# LabPower_test2.net
KiCad netlist of a schematic drawn in EAGLE
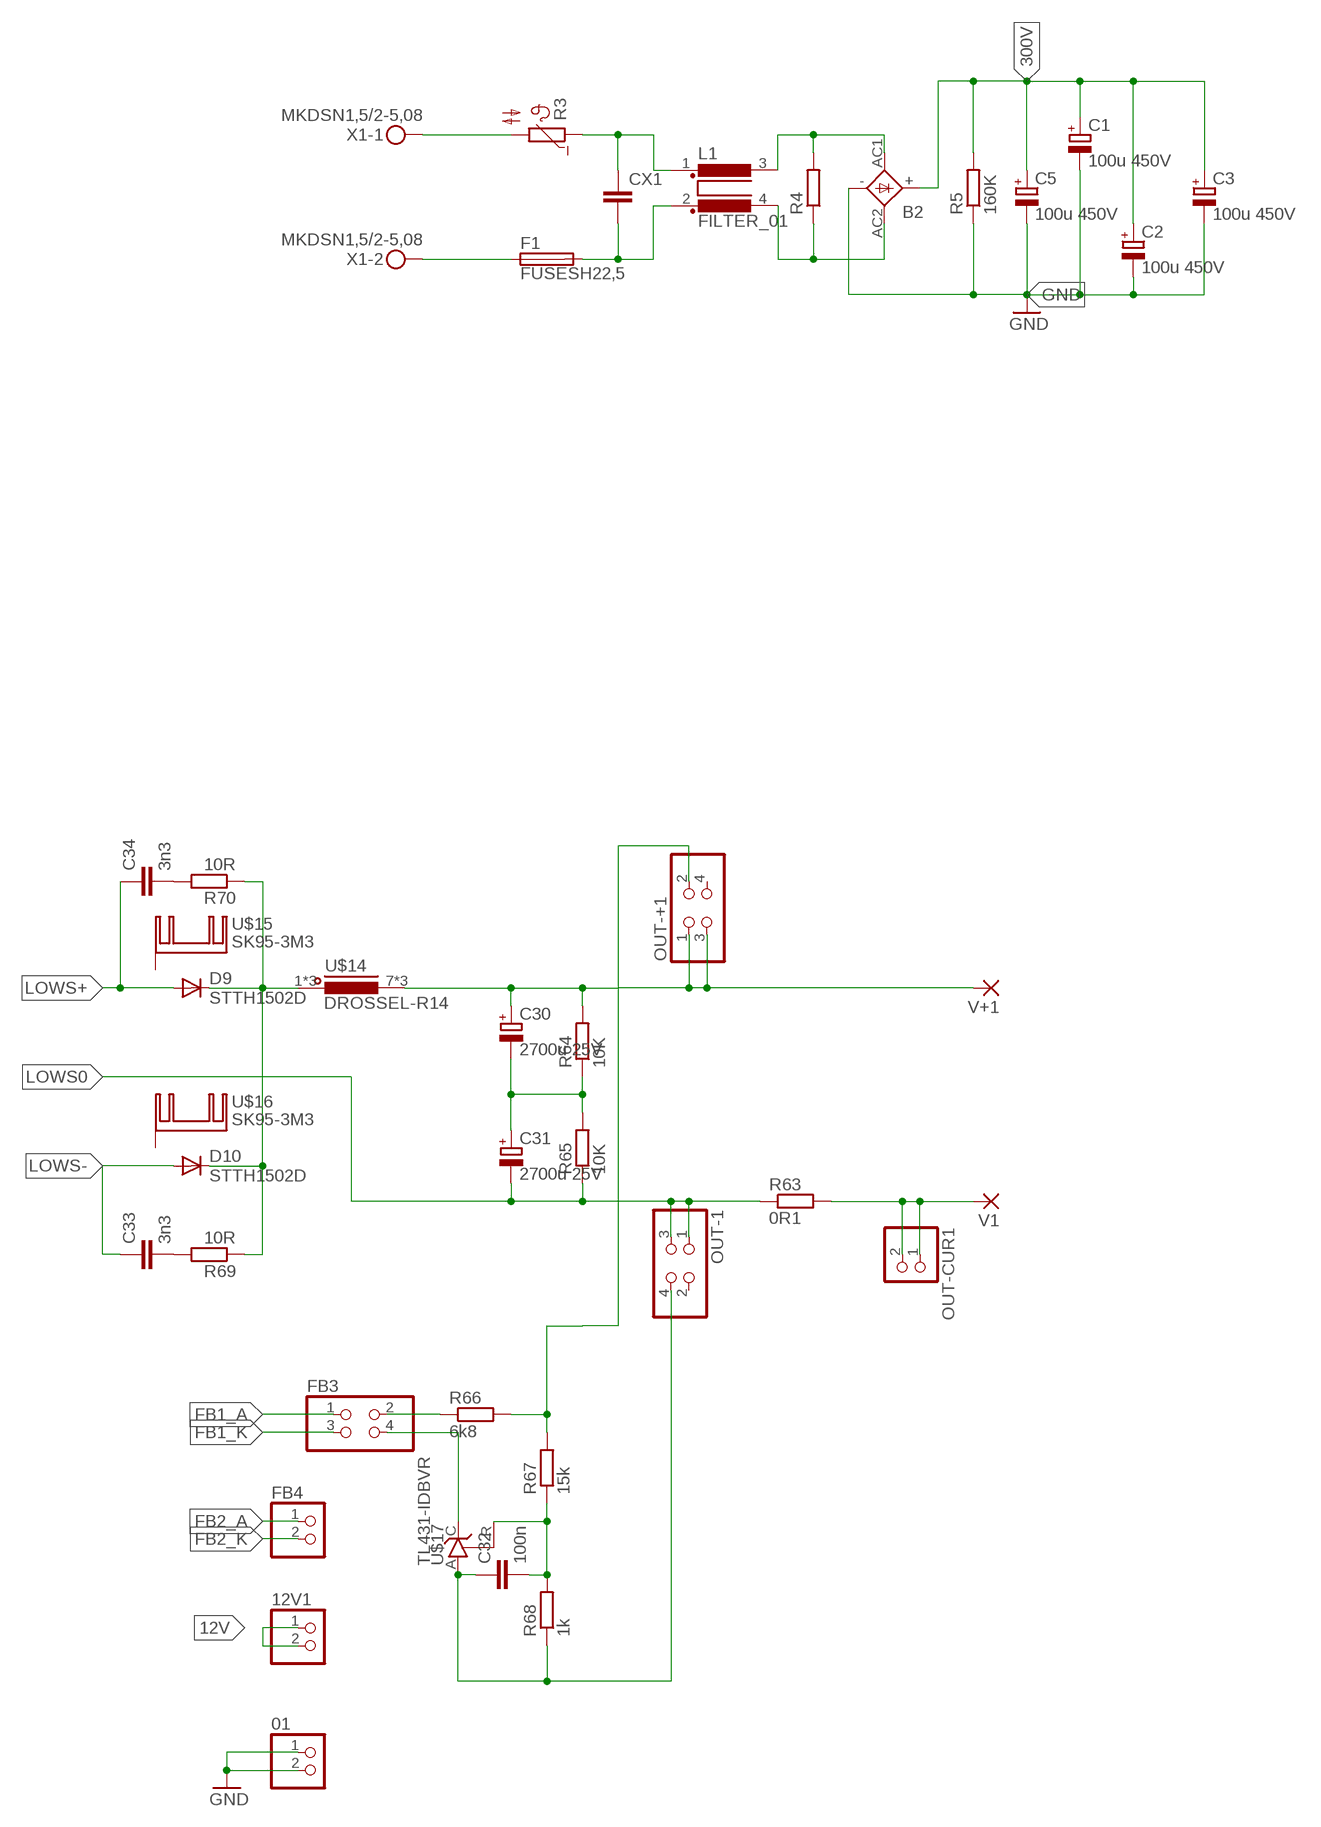
[diagram p0: schematic, sheet 1, part 1 of 2]
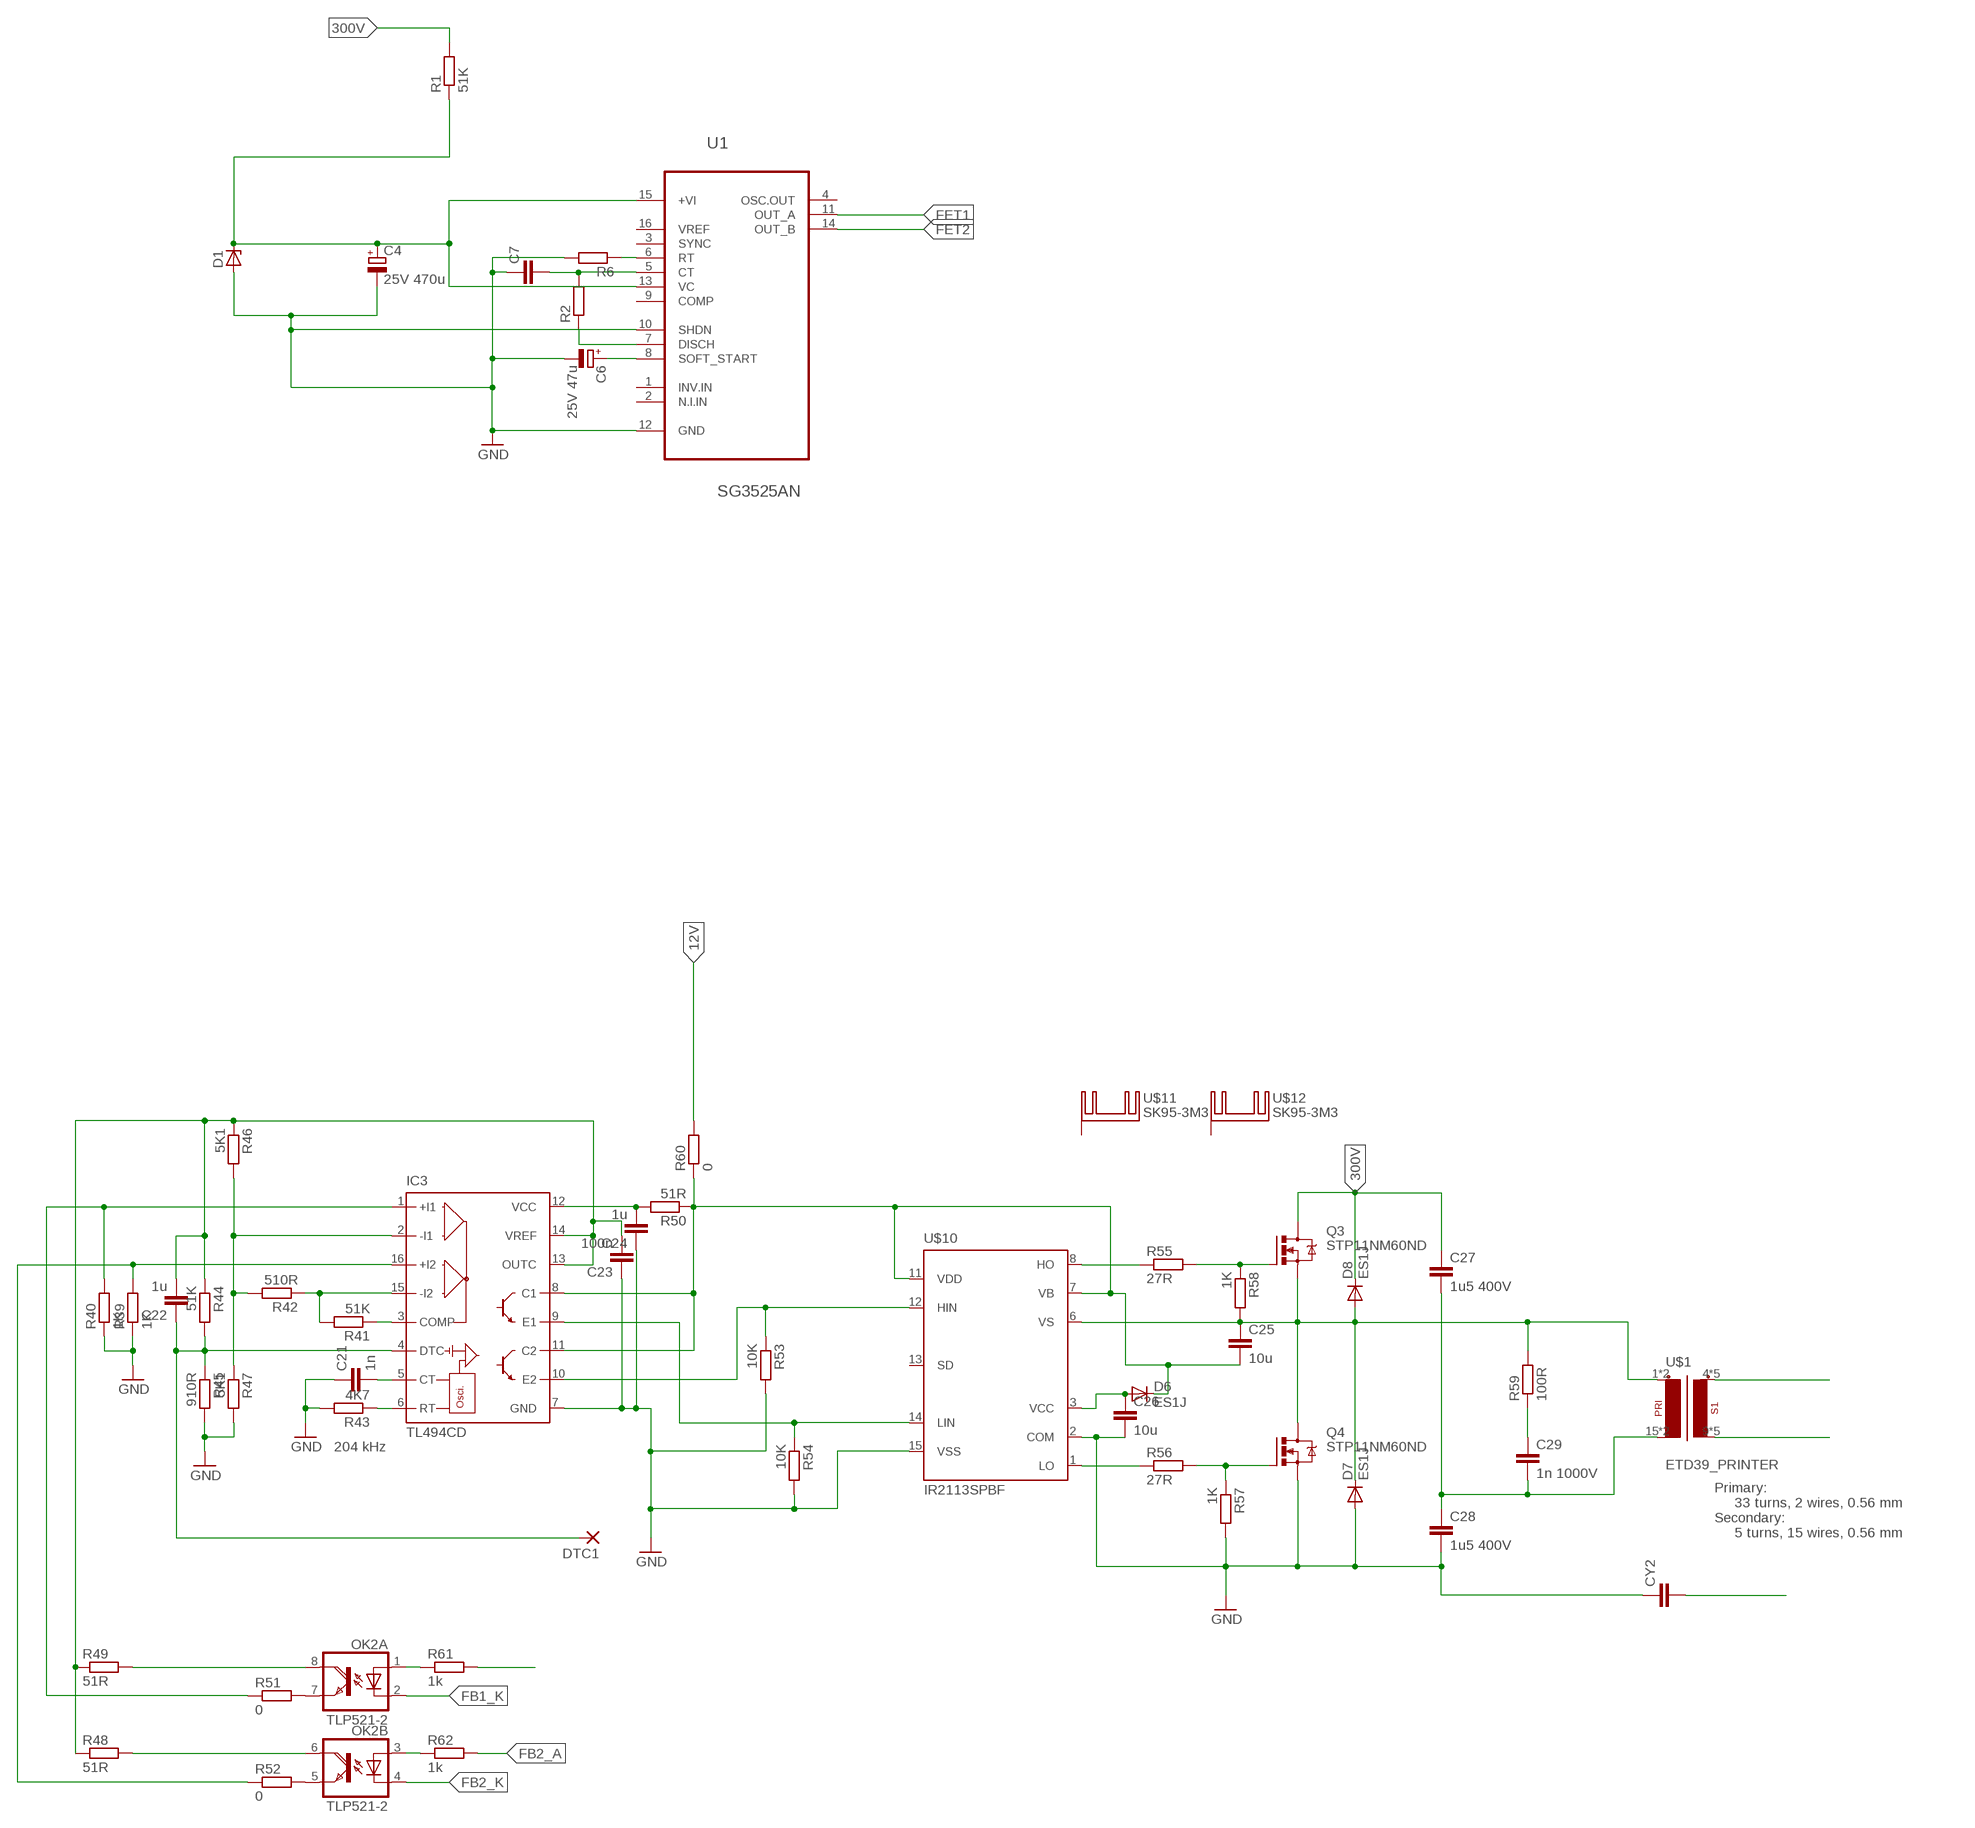
[diagram p1: schematic, sheet 1, part 2 of 2]

(export (version "E")
  (design (tool "Eeschema 10.0.6"))
  (components
    (comp (ref "01")
      (value "PINHD-1X2")
      (footprint "eagle-import:1X02")
      (libsource (lib "eagle-import") (part "PINHD-1X2"))
    )
    (comp (ref "12V1")
      (value "PINHD-1X2")
      (footprint "eagle-import:1X02")
      (libsource (lib "eagle-import") (part "PINHD-1X2"))
    )
    (comp (ref "B2")
      (value "KBL")
      (footprint "eagle-import:KBL")
      (libsource (lib "eagle-import") (part "KBL"))
    )
    (comp (ref "C1")
      (value "100u 450V")
      (footprint "eagle-import:EB22,5D")
      (libsource (lib "eagle-import") (part "CPOL-EUE10-22.5"))
    )
    (comp (ref "C2")
      (value "100u 450V")
      (footprint "eagle-import:EB22,5D")
      (libsource (lib "eagle-import") (part "CPOL-EUE10-22.5"))
    )
    (comp (ref "C3")
      (value "100u 450V")
      (footprint "eagle-import:EB22,5D")
      (libsource (lib "eagle-import") (part "CPOL-EUE10-22.5"))
    )
    (comp (ref "C4")
      (value "25V 470u")
      (footprint "eagle-import:E2,5-7")
      (libsource (lib "eagle-import") (part "CPOL-EUE2.5-7"))
    )
    (comp (ref "C5")
      (value "100u 450V")
      (footprint "eagle-import:EB22,5D")
      (libsource (lib "eagle-import") (part "CPOL-EUE10-22.5"))
    )
    (comp (ref "C6")
      (value "25V 47u")
      (footprint "eagle-import:E2,5-7")
      (libsource (lib "eagle-import") (part "CPOL-EUE2.5-7"))
    )
    (comp (ref "C7")
      (value "C-EUC0805")
      (footprint "eagle-import:C0805")
      (libsource (lib "eagle-import") (part "C-EUC0805"))
    )
    (comp (ref "C21")
      (value "1n")
      (footprint "eagle-import:C0805")
      (libsource (lib "eagle-import") (part "C-EUC0805"))
    )
    (comp (ref "C22")
      (value "1u")
      (footprint "eagle-import:C0805")
      (libsource (lib "eagle-import") (part "C-EUC0805"))
    )
    (comp (ref "C23")
      (value "100n")
      (footprint "eagle-import:C0805")
      (libsource (lib "eagle-import") (part "C-EUC0805"))
    )
    (comp (ref "C24")
      (value "1u")
      (footprint "eagle-import:C0805")
      (libsource (lib "eagle-import") (part "C-EUC0805"))
    )
    (comp (ref "C25")
      (value "10u")
      (footprint "eagle-import:C0805")
      (libsource (lib "eagle-import") (part "C-EUC0805"))
    )
    (comp (ref "C26")
      (value "10u")
      (footprint "eagle-import:C0805")
      (libsource (lib "eagle-import") (part "C-EUC0805"))
    )
    (comp (ref "C27")
      (value "1u5 400V")
      (footprint "eagle-import:C225-087X268")
      (libsource (lib "eagle-import") (part "C-EU225-087X268"))
    )
    (comp (ref "C28")
      (value "1u5 400V")
      (footprint "eagle-import:C225-087X268")
      (libsource (lib "eagle-import") (part "C-EU225-087X268"))
    )
    (comp (ref "C29")
      (value "1n 1000V")
      (footprint "eagle-import:C050-025X075")
      (libsource (lib "eagle-import") (part "C-EU050-025X075"))
    )
    (comp (ref "C30")
      (value "2700u 25V")
      (footprint "eagle-import:E7,5-18")
      (libsource (lib "eagle-import") (part "CPOL-EUE7.5-18"))
    )
    (comp (ref "C31")
      (value "2700u 25V")
      (footprint "eagle-import:E7,5-18")
      (libsource (lib "eagle-import") (part "CPOL-EUE7.5-18"))
    )
    (comp (ref "C32")
      (value "100n")
      (footprint "eagle-import:C0805")
      (libsource (lib "eagle-import") (part "C-EUC0805"))
    )
    (comp (ref "C33")
      (value "3n3")
      (footprint "eagle-import:C0805")
      (libsource (lib "eagle-import") (part "C-EUC0805"))
    )
    (comp (ref "C34")
      (value "3n3")
      (footprint "eagle-import:C0805")
      (libsource (lib "eagle-import") (part "C-EUC0805"))
    )
    (comp (ref "CX1")
      (value "CXXC15B8")
      (footprint "eagle-import:XC15B8")
      (libsource (lib "eagle-import") (part "CXXC15B8"))
    )
    (comp (ref "CY2")
      (value "CYYC10B4")
      (footprint "eagle-import:YC10B4")
      (libsource (lib "eagle-import") (part "CYYC10B4"))
    )
    (comp (ref "D1")
      (value "ZENER-DIODEDO41Z10")
      (footprint "eagle-import:DO41Z10")
      (libsource (lib "eagle-import") (part "ZENER-DIODEDO41Z10"))
    )
    (comp (ref "D6")
      (value "ES1J")
      (footprint "eagle-import:DO214AC")
      (libsource (lib "eagle-import") (part "DIODE-DO214AC"))
    )
    (comp (ref "D7")
      (value "ES1J")
      (footprint "eagle-import:DO214AC")
      (libsource (lib "eagle-import") (part "DIODE-DO214AC"))
    )
    (comp (ref "D8")
      (value "ES1J")
      (footprint "eagle-import:DO214AC")
      (libsource (lib "eagle-import") (part "DIODE-DO214AC"))
    )
    (comp (ref "D9")
      (value "STTH1502D")
      (footprint "eagle-import:DO220S")
      (libsource (lib "eagle-import") (part "DIODE-DO220S"))
    )
    (comp (ref "D10")
      (value "STTH1502D")
      (footprint "eagle-import:DO220S")
      (libsource (lib "eagle-import") (part "DIODE-DO220S"))
    )
    (comp (ref "DTC1")
      (value "SMD5")
      (footprint "eagle-import:SMD2,54-5,08")
      (libsource (lib "eagle-import") (part "SMD5"))
    )
    (comp (ref "F1")
      (value "FUSESH22,5")
      (footprint "eagle-import:SH22,5")
      (libsource (lib "eagle-import") (part "FUSESH22,5"))
    )
    (comp (ref "FB3")
      (value "PINHD-2X2")
      (footprint "eagle-import:2X02")
      (libsource (lib "eagle-import") (part "PINHD-2X2"))
    )
    (comp (ref "FB4")
      (value "PINHD-1X2")
      (footprint "eagle-import:1X02")
      (libsource (lib "eagle-import") (part "PINHD-1X2"))
    )
    (comp (ref "IC3")
      (value "TL494CD")
      (footprint "eagle-import:SO16")
      (libsource (lib "eagle-import") (part "TL494DC"))
    )
    (comp (ref "L1")
      (value "FILTER_01")
      (footprint "eagle-import:82721K")
      (libsource (lib "eagle-import") (part "FILTER_01"))
    )
    (comp (ref "OK2")
      (value "TLP521-2")
      (footprint "eagle-import:DIL08")
      (libsource (lib "eagle-import") (part "TIL198"))
    )
    (comp (ref "OUT-+1")
      (value "PINHD-2X2")
      (footprint "eagle-import:2X02")
      (libsource (lib "eagle-import") (part "PINHD-2X2"))
    )
    (comp (ref "OUT-1")
      (value "PINHD-2X2")
      (footprint "eagle-import:2X02")
      (libsource (lib "eagle-import") (part "PINHD-2X2"))
    )
    (comp (ref "OUT-CUR1")
      (value "PINHD-1X2")
      (footprint "eagle-import:1X02")
      (libsource (lib "eagle-import") (part "PINHD-1X2"))
    )
    (comp (ref "Q3")
      (value "STP11NM60ND")
      (footprint "eagle-import:TO220BV")
      (libsource (lib "eagle-import") (part "IRF740"))
    )
    (comp (ref "Q4")
      (value "STP11NM60ND")
      (footprint "eagle-import:TO220BV")
      (libsource (lib "eagle-import") (part "IRF740"))
    )
    (comp (ref "R1")
      (value "51K")
      (footprint "eagle-import:SQP-5")
      (libsource (lib "eagle-import") (part "R_SQP-5"))
    )
    (comp (ref "R2")
      (value "R-EU_R0805")
      (footprint "eagle-import:R0805")
      (libsource (lib "eagle-import") (part "R-EU_R0805"))
    )
    (comp (ref "R3")
      (value "B57164")
      (footprint "eagle-import:B57164")
      (fields (field (name "MPN") "B57164K474K52"))
      (libsource (lib "eagle-import") (part "B57164"))
    )
    (comp (ref "R4")
      (value "R-EU_0309/10")
      (footprint "eagle-import:0309_10")
      (libsource (lib "eagle-import") (part "R-EU_0309/10"))
    )
    (comp (ref "R5")
      (value "160K")
      (footprint "eagle-import:0207_12")
      (libsource (lib "eagle-import") (part "R-EU_0207/12"))
    )
    (comp (ref "R6")
      (value "R-EU_R0805")
      (footprint "eagle-import:R0805")
      (libsource (lib "eagle-import") (part "R-EU_R0805"))
    )
    (comp (ref "R39")
      (value "1K")
      (footprint "eagle-import:R0805")
      (libsource (lib "eagle-import") (part "R-EU_R0805"))
    )
    (comp (ref "R40")
      (value "1K")
      (footprint "eagle-import:R0805")
      (libsource (lib "eagle-import") (part "R-EU_R0805"))
    )
    (comp (ref "R41")
      (value "51K")
      (footprint "eagle-import:R0805")
      (libsource (lib "eagle-import") (part "R-EU_R0805"))
    )
    (comp (ref "R42")
      (value "510R")
      (footprint "eagle-import:R0805")
      (libsource (lib "eagle-import") (part "R-EU_R0805"))
    )
    (comp (ref "R43")
      (value "4K7")
      (footprint "eagle-import:R0805")
      (libsource (lib "eagle-import") (part "R-EU_R0805"))
    )
    (comp (ref "R44")
      (value "51K")
      (footprint "eagle-import:R0805")
      (libsource (lib "eagle-import") (part "R-EU_R0805"))
    )
    (comp (ref "R45")
      (value "910R")
      (footprint "eagle-import:R0805")
      (libsource (lib "eagle-import") (part "R-EU_R0805"))
    )
    (comp (ref "R46")
      (value "5K1")
      (footprint "eagle-import:R0805")
      (libsource (lib "eagle-import") (part "R-EU_R0805"))
    )
    (comp (ref "R47")
      (value "5K1")
      (footprint "eagle-import:R0805")
      (libsource (lib "eagle-import") (part "R-EU_R0805"))
    )
    (comp (ref "R48")
      (value "51R")
      (footprint "eagle-import:R0805")
      (libsource (lib "eagle-import") (part "R-EU_R0805"))
    )
    (comp (ref "R49")
      (value "51R")
      (footprint "eagle-import:R0805")
      (libsource (lib "eagle-import") (part "R-EU_R0805"))
    )
    (comp (ref "R50")
      (value "51R")
      (footprint "eagle-import:R0805")
      (libsource (lib "eagle-import") (part "R-EU_R0805"))
    )
    (comp (ref "R51")
      (value "0")
      (footprint "eagle-import:R1206")
      (libsource (lib "eagle-import") (part "R-EU_R1206"))
    )
    (comp (ref "R52")
      (value "0")
      (footprint "eagle-import:R1206")
      (libsource (lib "eagle-import") (part "R-EU_R1206"))
    )
    (comp (ref "R53")
      (value "10K")
      (footprint "eagle-import:R0805")
      (libsource (lib "eagle-import") (part "R-EU_R0805"))
    )
    (comp (ref "R54")
      (value "10K")
      (footprint "eagle-import:R0805")
      (libsource (lib "eagle-import") (part "R-EU_R0805"))
    )
    (comp (ref "R55")
      (value "27R")
      (footprint "eagle-import:R1206")
      (libsource (lib "eagle-import") (part "R-EU_R1206"))
    )
    (comp (ref "R56")
      (value "27R")
      (footprint "eagle-import:R1206")
      (libsource (lib "eagle-import") (part "R-EU_R1206"))
    )
    (comp (ref "R57")
      (value "1K")
      (footprint "eagle-import:R0805")
      (libsource (lib "eagle-import") (part "R-EU_R0805"))
    )
    (comp (ref "R58")
      (value "1K")
      (footprint "eagle-import:R0805")
      (libsource (lib "eagle-import") (part "R-EU_R0805"))
    )
    (comp (ref "R59")
      (value "100R")
      (footprint "eagle-import:0617_17")
      (libsource (lib "eagle-import") (part "R-EU_0617/17"))
    )
    (comp (ref "R60")
      (value "0")
      (footprint "eagle-import:R1206")
      (libsource (lib "eagle-import") (part "R-EU_R1206"))
    )
    (comp (ref "R61")
      (value "1k")
      (footprint "eagle-import:R0805")
      (libsource (lib "eagle-import") (part "R-EU_R0805"))
    )
    (comp (ref "R62")
      (value "1k")
      (footprint "eagle-import:R0805")
      (libsource (lib "eagle-import") (part "R-EU_R0805"))
    )
    (comp (ref "R63")
      (value "0R1")
      (footprint "eagle-import:SQP-10")
      (libsource (lib "eagle-import") (part "R_SQP-10"))
    )
    (comp (ref "R64")
      (value "10K")
      (footprint "eagle-import:0207_10")
      (libsource (lib "eagle-import") (part "R-EU_0207/10"))
    )
    (comp (ref "R65")
      (value "10K")
      (footprint "eagle-import:0207_10")
      (libsource (lib "eagle-import") (part "R-EU_0207/10"))
    )
    (comp (ref "R66")
      (value "6k8")
      (footprint "eagle-import:R0805")
      (libsource (lib "eagle-import") (part "R-EU_R0805"))
    )
    (comp (ref "R67")
      (value "15k")
      (footprint "eagle-import:R0805")
      (libsource (lib "eagle-import") (part "R-EU_R0805"))
    )
    (comp (ref "R68")
      (value "1k")
      (footprint "eagle-import:R0805")
      (libsource (lib "eagle-import") (part "R-EU_R0805"))
    )
    (comp (ref "R69")
      (value "10R")
      (footprint "eagle-import:R0805")
      (libsource (lib "eagle-import") (part "R-EU_R0805"))
    )
    (comp (ref "R70")
      (value "10R")
      (footprint "eagle-import:R0805")
      (libsource (lib "eagle-import") (part "R-EU_R0805"))
    )
    (comp (ref "U$1")
      (value "ETD39_PRINTER")
      (footprint "eagle-import:ETD39_16PIN")
      (libsource (lib "eagle-import") (part "ETD39_PRINTER"))
    )
    (comp (ref "U$10")
      (value "IR2113SPBF")
      (footprint "eagle-import:SO16W")
      (libsource (lib "eagle-import") (part "IR2113SPBF"))
    )
    (comp (ref "U$11")
      (value "SK95-3M3")
      (footprint "eagle-import:SK95-3M3")
      (libsource (lib "eagle-import") (part "SK95-3M3"))
    )
    (comp (ref "U$12")
      (value "SK95-3M3")
      (footprint "eagle-import:SK95-3M3")
      (libsource (lib "eagle-import") (part "SK95-3M3"))
    )
    (comp (ref "U$14")
      (value "DROSSEL-R14")
      (footprint "eagle-import:RM14")
      (libsource (lib "eagle-import") (part "DROSSEL-R14"))
    )
    (comp (ref "U$15")
      (value "SK95-3M3")
      (footprint "eagle-import:SK95-3M3")
      (libsource (lib "eagle-import") (part "SK95-3M3"))
    )
    (comp (ref "U$16")
      (value "SK95-3M3")
      (footprint "eagle-import:SK95-3M3")
      (libsource (lib "eagle-import") (part "SK95-3M3"))
    )
    (comp (ref "U$17")
      (value "TL431-IDBVR")
      (footprint "eagle-import:SOT23-5")
      (libsource (lib "eagle-import") (part "TL431-IDBVR"))
    )
    (comp (ref "U1")
      (value "SG3525AN")
      (footprint "eagle-import:DIP254P762X510-16")
      (libsource (lib "eagle-import") (part "SG3525AN"))
    )
    (comp (ref "V+1")
      (value "3,81/1,4")
      (footprint "eagle-import:3,81_1,4")
      (libsource (lib "eagle-import") (part "3,81/1,4"))
    )
    (comp (ref "V1")
      (value "3,81/1,4")
      (footprint "eagle-import:3,81_1,4")
      (libsource (lib "eagle-import") (part "3,81/1,4"))
    )
    (comp (ref "X1")
      (value "MKDSN1,5/2-5,08")
      (footprint "eagle-import:MKDSN1,5_2-5,08")
      (libsource (lib "eagle-import") (part "MKDSN1,5/2-5,08"))
    )
  )
  (nets
    (net (code "1") (name "12V") (class "Default")
      (node (ref "12V1") (pin "1") (pinfunction "1_1") (pintype "passive"))
      (node (ref "12V1") (pin "2") (pinfunction "2_2") (pintype "passive"))
      (node (ref "R60") (pin "2") (pinfunction "2_2") (pintype "passive"))
    )
    (net (code "2") (name "300V") (class "Default")
      (node (ref "B2") (pin "+") (pinfunction "+_+") (pintype "passive"))
      (node (ref "C1") (pin "+") (pinfunction "+_+") (pintype "passive"))
      (node (ref "C2") (pin "+") (pinfunction "+_+") (pintype "passive"))
      (node (ref "C27") (pin "1") (pinfunction "1_1") (pintype "passive"))
      (node (ref "C3") (pin "+") (pinfunction "+_+") (pintype "passive"))
      (node (ref "C5") (pin "+") (pinfunction "+_+") (pintype "passive"))
      (node (ref "D8") (pin "C") (pinfunction "C_C") (pintype "passive"))
      (node (ref "Q3") (pin "D") (pinfunction "D_D") (pintype "passive"))
      (node (ref "R1") (pin "2") (pinfunction "2_2") (pintype "passive"))
      (node (ref "R5") (pin "2") (pinfunction "2_2") (pintype "passive"))
    )
    (net (code "3") (name "FB1_A") (class "Default")
      (node (ref "FB3") (pin "1") (pinfunction "1_1") (pintype "passive"))
    )
    (net (code "4") (name "FB1_K") (class "Default")
      (node (ref "FB3") (pin "3") (pinfunction "3_3") (pintype "passive"))
      (node (ref "OK2") (pin "2") (pinfunction "C_2") (pintype "passive"))
    )
    (net (code "5") (name "FB2_A") (class "Default")
      (node (ref "FB4") (pin "1") (pinfunction "1_1") (pintype "passive"))
      (node (ref "R62") (pin "2") (pinfunction "2_2") (pintype "passive"))
    )
    (net (code "6") (name "FB2_K") (class "Default")
      (node (ref "FB4") (pin "2") (pinfunction "2_2") (pintype "passive"))
      (node (ref "OK2") (pin "4") (pinfunction "C_4") (pintype "passive"))
    )
    (net (code "7") (name "FET1") (class "Default")
      (node (ref "U1") (pin "11") (pinfunction "OUT_A_11") (pintype "output"))
    )
    (net (code "8") (name "FET2") (class "Default")
      (node (ref "U1") (pin "14") (pinfunction "OUT_B_14") (pintype "output"))
    )
    (net (code "9") (name "GND") (class "Default")
      (node (ref "01") (pin "1") (pinfunction "1_1") (pintype "passive"))
      (node (ref "01") (pin "2") (pinfunction "2_2") (pintype "passive"))
      (node (ref "B2") (pin "-") (pinfunction "-_-") (pintype "passive"))
      (node (ref "C1") (pin "-") (pinfunction "-_-") (pintype "passive"))
      (node (ref "C2") (pin "-") (pinfunction "-_-") (pintype "passive"))
      (node (ref "C21") (pin "1") (pinfunction "1_1") (pintype "passive"))
      (node (ref "C23") (pin "1") (pinfunction "1_1") (pintype "passive"))
      (node (ref "C24") (pin "1") (pinfunction "1_1") (pintype "passive"))
      (node (ref "C26") (pin "2") (pinfunction "2_2") (pintype "passive"))
      (node (ref "C28") (pin "2") (pinfunction "2_2") (pintype "passive"))
      (node (ref "C3") (pin "-") (pinfunction "-_-") (pintype "passive"))
      (node (ref "C4") (pin "-") (pinfunction "-_-") (pintype "passive"))
      (node (ref "C5") (pin "-") (pinfunction "-_-") (pintype "passive"))
      (node (ref "C6") (pin "-") (pinfunction "-_-") (pintype "passive"))
      (node (ref "C7") (pin "1") (pinfunction "1_1") (pintype "passive"))
      (node (ref "CY2") (pin "1") (pinfunction "1_1") (pintype "passive"))
      (node (ref "D1") (pin "A") (pinfunction "A_A") (pintype "passive"))
      (node (ref "D7") (pin "A") (pinfunction "A_A") (pintype "passive"))
      (node (ref "IC3") (pin "7") (pinfunction "GND_7") (pintype "power_in"))
      (node (ref "Q4") (pin "S") (pinfunction "S_S") (pintype "passive"))
      (node (ref "R39") (pin "1") (pinfunction "1_1") (pintype "passive"))
      (node (ref "R40") (pin "1") (pinfunction "1_1") (pintype "passive"))
      (node (ref "R43") (pin "2") (pinfunction "2_2") (pintype "passive"))
      (node (ref "R45") (pin "2") (pinfunction "2_2") (pintype "passive"))
      (node (ref "R47") (pin "2") (pinfunction "2_2") (pintype "passive"))
      (node (ref "R5") (pin "1") (pinfunction "1_1") (pintype "passive"))
      (node (ref "R53") (pin "2") (pinfunction "2_2") (pintype "passive"))
      (node (ref "R54") (pin "2") (pinfunction "2_2") (pintype "passive"))
      (node (ref "R57") (pin "2") (pinfunction "2_2") (pintype "passive"))
      (node (ref "R6") (pin "2") (pinfunction "2_2") (pintype "passive"))
      (node (ref "U$10") (pin "15") (pinfunction "VSS_15") (pintype "power_in"))
      (node (ref "U$10") (pin "2") (pinfunction "COM_2") (pintype "power_in"))
      (node (ref "U1") (pin "10") (pinfunction "SHDN_10") (pintype "input"))
      (node (ref "U1") (pin "12") (pinfunction "GND_12") (pintype "passive"))
    )
    (net (code "10") (name "LOWS+") (class "Default")
      (node (ref "C34") (pin "1") (pinfunction "1_1") (pintype "passive"))
      (node (ref "D9") (pin "A") (pinfunction "A_A") (pintype "passive"))
    )
    (net (code "11") (name "LOWS-") (class "Default")
      (node (ref "C33") (pin "1") (pinfunction "1_1") (pintype "passive"))
      (node (ref "D10") (pin "A") (pinfunction "A_A") (pintype "passive"))
    )
    (net (code "12") (name "LOWS0") (class "Default")
      (node (ref "C31") (pin "-") (pinfunction "-_-") (pintype "passive"))
      (node (ref "CY2") (pin "2") (pinfunction "2_2") (pintype "passive"))
      (node (ref "OUT-1") (pin "1") (pinfunction "1_1") (pintype "passive"))
      (node (ref "OUT-1") (pin "3") (pinfunction "3_3") (pintype "passive"))
      (node (ref "R63") (pin "P$1") (pinfunction "1_P$1") (pintype "passive"))
      (node (ref "R65") (pin "1") (pinfunction "1_1") (pintype "passive"))
    )
    (net (code "13") (name "Net-(B2-AC1)") (class "Default")
      (node (ref "B2") (pin "AC2") (pinfunction "AC1_AC2") (pintype "passive"))
      (node (ref "L1") (pin "4") (pinfunction "4_4") (pintype "passive"))
      (node (ref "R4") (pin "1") (pinfunction "1_1") (pintype "passive"))
    )
    (net (code "14") (name "Net-(B2-AC2)") (class "Default")
      (node (ref "B2") (pin "AC1") (pinfunction "AC2_AC1") (pintype "passive"))
      (node (ref "L1") (pin "3") (pinfunction "2_3") (pintype "passive"))
      (node (ref "R4") (pin "2") (pinfunction "2_2") (pintype "passive"))
    )
    (net (code "15") (name "Net-(C27-Pad2)") (class "Default")
      (node (ref "C27") (pin "2") (pinfunction "2_2") (pintype "passive"))
      (node (ref "C28") (pin "1") (pinfunction "1_1") (pintype "passive"))
      (node (ref "C29") (pin "2") (pinfunction "2_2") (pintype "passive"))
      (node (ref "U$1") (pin "15") (pinfunction "P1-2_15") (pintype "passive"))
      (node (ref "U$1") (pin "16") (pinfunction "P1-2_16") (pintype "passive"))
    )
    (net (code "16") (name "Net-(C29-Pad1)") (class "Default")
      (node (ref "C29") (pin "1") (pinfunction "1_1") (pintype "passive"))
      (node (ref "R59") (pin "1") (pinfunction "1_1") (pintype "passive"))
    )
    (net (code "17") (name "Net-(C30-Pad-)") (class "Default")
      (node (ref "C30") (pin "-") (pinfunction "-_-") (pintype "passive"))
      (node (ref "C31") (pin "+") (pinfunction "+_+") (pintype "passive"))
      (node (ref "R64") (pin "1") (pinfunction "1_1") (pintype "passive"))
      (node (ref "R65") (pin "2") (pinfunction "2_2") (pintype "passive"))
    )
    (net (code "18") (name "Net-(C32-Pad1)") (class "Default")
      (node (ref "C32") (pin "1") (pinfunction "1_1") (pintype "passive"))
      (node (ref "OUT-1") (pin "4") (pinfunction "4_4") (pintype "passive"))
      (node (ref "R68") (pin "1") (pinfunction "1_1") (pintype "passive"))
      (node (ref "U$17") (pin "A") (pinfunction "A_A") (pintype "passive"))
    )
    (net (code "19") (name "Net-(C32-Pad2)") (class "Default")
      (node (ref "C32") (pin "2") (pinfunction "2_2") (pintype "passive"))
      (node (ref "R67") (pin "1") (pinfunction "1_1") (pintype "passive"))
      (node (ref "R68") (pin "2") (pinfunction "2_2") (pintype "passive"))
      (node (ref "U$17") (pin "R") (pinfunction "R_R") (pintype "passive"))
    )
    (net (code "20") (name "Net-(C33-Pad2)") (class "Default")
      (node (ref "C33") (pin "2") (pinfunction "2_2") (pintype "passive"))
      (node (ref "R69") (pin "2") (pinfunction "2_2") (pintype "passive"))
    )
    (net (code "21") (name "Net-(C34-Pad2)") (class "Default")
      (node (ref "C34") (pin "2") (pinfunction "2_2") (pintype "passive"))
      (node (ref "R70") (pin "2") (pinfunction "2_2") (pintype "passive"))
    )
    (net (code "22") (name "Net-(CX1-Pad1)") (class "Default")
      (node (ref "CX1") (pin "1") (pinfunction "1_1") (pintype "passive"))
      (node (ref "L1") (pin "1") (pinfunction "1_1") (pintype "passive"))
      (node (ref "R3") (pin "1") (pinfunction "1_1") (pintype "passive"))
    )
    (net (code "23") (name "Net-(D10-PadC)") (class "Default")
      (node (ref "D10") (pin "C") (pinfunction "C_C") (pintype "passive"))
      (node (ref "D9") (pin "C") (pinfunction "C_C") (pintype "passive"))
      (node (ref "R69") (pin "1") (pinfunction "1_1") (pintype "passive"))
      (node (ref "R70") (pin "1") (pinfunction "1_1") (pintype "passive"))
      (node (ref "U$14") (pin "1") (pinfunction "1_1") (pintype "passive"))
      (node (ref "U$14") (pin "2") (pinfunction "1_2") (pintype "passive"))
      (node (ref "U$14") (pin "3") (pinfunction "1_3") (pintype "passive"))
    )
    (net (code "24") (name "Net-(DTC1-P)") (class "Default")
      (node (ref "C22") (pin "1") (pinfunction "1_1") (pintype "passive"))
      (node (ref "DTC1") (pin "1") (pinfunction "P_1") (pintype "passive"))
      (node (ref "IC3") (pin "4") (pinfunction "DTC_4") (pintype "input"))
      (node (ref "R44") (pin "2") (pinfunction "2_2") (pintype "passive"))
      (node (ref "R45") (pin "1") (pinfunction "1_1") (pintype "passive"))
    )
    (net (code "25") (name "Net-(FB3-Pad2)") (class "Default")
      (node (ref "FB3") (pin "2") (pinfunction "2_2") (pintype "passive"))
      (node (ref "R66") (pin "1") (pinfunction "1_1") (pintype "passive"))
    )
    (net (code "26") (name "Net-(FB3-Pad4)") (class "Default")
      (node (ref "FB3") (pin "4") (pinfunction "4_4") (pintype "passive"))
      (node (ref "U$17") (pin "C") (pinfunction "C_C") (pintype "passive"))
    )
    (net (code "27") (name "Net-(IC3-+I1)") (class "Default")
      (node (ref "IC3") (pin "1") (pinfunction "+I1_1") (pintype "input"))
      (node (ref "R40") (pin "2") (pinfunction "2_2") (pintype "passive"))
      (node (ref "R51") (pin "1") (pinfunction "1_1") (pintype "passive"))
    )
    (net (code "28") (name "Net-(IC3-+I2)") (class "Default")
      (node (ref "IC3") (pin "16") (pinfunction "+I2_16") (pintype "input"))
      (node (ref "R39") (pin "2") (pinfunction "2_2") (pintype "passive"))
      (node (ref "R52") (pin "1") (pinfunction "1_1") (pintype "passive"))
    )
    (net (code "29") (name "Net-(IC3--I1)") (class "Default")
      (node (ref "IC3") (pin "2") (pinfunction "-I1_2") (pintype "input"))
      (node (ref "R42") (pin "2") (pinfunction "2_2") (pintype "passive"))
      (node (ref "R46") (pin "2") (pinfunction "2_2") (pintype "passive"))
      (node (ref "R47") (pin "1") (pinfunction "1_1") (pintype "passive"))
    )
    (net (code "30") (name "Net-(IC3--I2)") (class "Default")
      (node (ref "IC3") (pin "15") (pinfunction "-I2_15") (pintype "input"))
      (node (ref "R41") (pin "2") (pinfunction "2_2") (pintype "passive"))
      (node (ref "R42") (pin "1") (pinfunction "1_1") (pintype "passive"))
    )
    (net (code "31") (name "Net-(IC3-C1)") (class "Default")
      (node (ref "C25") (pin "2") (pinfunction "2_2") (pintype "passive"))
      (node (ref "D6") (pin "C") (pinfunction "C_C") (pintype "passive"))
      (node (ref "IC3") (pin "11") (pinfunction "C2_11") (pintype "passive"))
      (node (ref "IC3") (pin "8") (pinfunction "C1_8") (pintype "passive"))
      (node (ref "R50") (pin "1") (pinfunction "1_1") (pintype "passive"))
      (node (ref "R60") (pin "1") (pinfunction "1_1") (pintype "passive"))
      (node (ref "U$10") (pin "11") (pinfunction "VDD_11") (pintype "power_in"))
      (node (ref "U$10") (pin "7") (pinfunction "VB_7") (pintype "power_in"))
    )
    (net (code "32") (name "Net-(IC3-COMP)") (class "Default")
      (node (ref "IC3") (pin "3") (pinfunction "COMP_3") (pintype "passive"))
      (node (ref "R41") (pin "1") (pinfunction "1_1") (pintype "passive"))
    )
    (net (code "33") (name "Net-(IC3-CT)") (class "Default")
      (node (ref "C21") (pin "2") (pinfunction "2_2") (pintype "passive"))
      (node (ref "IC3") (pin "5") (pinfunction "CT_5") (pintype "input"))
    )
    (net (code "34") (name "Net-(IC3-E1)") (class "Default")
      (node (ref "IC3") (pin "9") (pinfunction "E1_9") (pintype "passive"))
      (node (ref "R54") (pin "1") (pinfunction "1_1") (pintype "passive"))
      (node (ref "U$10") (pin "14") (pinfunction "LIN_14") (pintype "input"))
    )
    (net (code "35") (name "Net-(IC3-E2)") (class "Default")
      (node (ref "IC3") (pin "10") (pinfunction "E2_10") (pintype "passive"))
      (node (ref "R53") (pin "1") (pinfunction "1_1") (pintype "passive"))
      (node (ref "U$10") (pin "12") (pinfunction "HIN_12") (pintype "input"))
    )
    (net (code "36") (name "Net-(IC3-OUTC)") (class "Default")
      (node (ref "C22") (pin "2") (pinfunction "2_2") (pintype "passive"))
      (node (ref "C23") (pin "2") (pinfunction "2_2") (pintype "passive"))
      (node (ref "IC3") (pin "13") (pinfunction "OUTC_13") (pintype "output"))
      (node (ref "IC3") (pin "14") (pinfunction "VREF_14") (pintype "input"))
      (node (ref "R44") (pin "1") (pinfunction "1_1") (pintype "passive"))
      (node (ref "R46") (pin "1") (pinfunction "1_1") (pintype "passive"))
      (node (ref "R48") (pin "1") (pinfunction "1_1") (pintype "passive"))
      (node (ref "R49") (pin "1") (pinfunction "1_1") (pintype "passive"))
    )
    (net (code "37") (name "Net-(IC3-RT)") (class "Default")
      (node (ref "IC3") (pin "6") (pinfunction "RT_6") (pintype "input"))
      (node (ref "R43") (pin "1") (pinfunction "1_1") (pintype "passive"))
    )
    (net (code "38") (name "Net-(IC3-VCC)") (class "Default")
      (node (ref "C24") (pin "2") (pinfunction "2_2") (pintype "passive"))
      (node (ref "IC3") (pin "12") (pinfunction "VCC_12") (pintype "power_in"))
      (node (ref "R50") (pin "2") (pinfunction "2_2") (pintype "passive"))
    )
    (net (code "39") (name "Net-(L1-3)") (class "Default")
      (node (ref "CX1") (pin "2") (pinfunction "2_2") (pintype "passive"))
      (node (ref "F1") (pin "2") (pinfunction "2_2") (pintype "passive"))
      (node (ref "L1") (pin "2") (pinfunction "3_2") (pintype "passive"))
    )
    (net (code "40") (name "Net-(OK2A-A)") (class "Default")
      (node (ref "OK2") (pin "1") (pinfunction "A_1") (pintype "passive"))
      (node (ref "R61") (pin "1") (pinfunction "1_1") (pintype "passive"))
    )
    (net (code "41") (name "Net-(OK2A-COL)") (class "Default")
      (node (ref "OK2") (pin "8") (pinfunction "COL_8") (pintype "passive"))
      (node (ref "R49") (pin "2") (pinfunction "2_2") (pintype "passive"))
    )
    (net (code "42") (name "Net-(OK2A-EMI)") (class "Default")
      (node (ref "OK2") (pin "7") (pinfunction "EMI_7") (pintype "passive"))
      (node (ref "R51") (pin "2") (pinfunction "2_2") (pintype "passive"))
    )
    (net (code "43") (name "Net-(OK2B-A)") (class "Default")
      (node (ref "OK2") (pin "3") (pinfunction "A_3") (pintype "passive"))
      (node (ref "R62") (pin "1") (pinfunction "1_1") (pintype "passive"))
    )
    (net (code "44") (name "Net-(OK2B-COL)") (class "Default")
      (node (ref "OK2") (pin "6") (pinfunction "COL_6") (pintype "passive"))
      (node (ref "R48") (pin "2") (pinfunction "2_2") (pintype "passive"))
    )
    (net (code "45") (name "Net-(OK2B-EMI)") (class "Default")
      (node (ref "OK2") (pin "5") (pinfunction "EMI_5") (pintype "passive"))
      (node (ref "R52") (pin "2") (pinfunction "2_2") (pintype "passive"))
    )
    (net (code "46") (name "Net-(OUT-+1-Pad2)") (class "Default")
      (node (ref "OUT-+1") (pin "2") (pinfunction "2_2") (pintype "passive"))
      (node (ref "R66") (pin "2") (pinfunction "2_2") (pintype "passive"))
      (node (ref "R67") (pin "2") (pinfunction "2_2") (pintype "passive"))
    )
    (net (code "47") (name "Net-(Q3-PadG)") (class "Default")
      (node (ref "Q3") (pin "G") (pinfunction "G_G") (pintype "passive"))
      (node (ref "R55") (pin "2") (pinfunction "2_2") (pintype "passive"))
      (node (ref "R58") (pin "1") (pinfunction "1_1") (pintype "passive"))
    )
    (net (code "48") (name "Net-(Q4-PadG)") (class "Default")
      (node (ref "Q4") (pin "G") (pinfunction "G_G") (pintype "passive"))
      (node (ref "R56") (pin "2") (pinfunction "2_2") (pintype "passive"))
      (node (ref "R57") (pin "1") (pinfunction "1_1") (pintype "passive"))
    )
    (net (code "49") (name "Net-(R63-2)") (class "Default")
      (node (ref "OUT-CUR1") (pin "1") (pinfunction "1_1") (pintype "passive"))
      (node (ref "OUT-CUR1") (pin "2") (pinfunction "2_2") (pintype "passive"))
      (node (ref "R63") (pin "P$2") (pinfunction "2_P$2") (pintype "passive"))
      (node (ref "V1") (pin "1") (pinfunction "P_1") (pintype "passive"))
    )
    (net (code "50") (name "Net-(U$1-S1-1-Pad4)") (class "Default")
      (node (ref "U$1") (pin "4") (pinfunction "S1-1_4") (pintype "passive"))
      (node (ref "U$1") (pin "5") (pinfunction "S1-1_5") (pintype "passive"))
      (node (ref "U$1") (pin "6") (pinfunction "S1-1_6") (pintype "passive"))
      (node (ref "U$1") (pin "7") (pinfunction "S1-1_7") (pintype "passive"))
      (node (ref "U$1") (pin "8") (pinfunction "S1-1_8") (pintype "passive"))
    )
    (net (code "51") (name "Net-(U$1-S1-2-Pad10)") (class "Default")
      (node (ref "U$1") (pin "10") (pinfunction "S1-2_10") (pintype "passive"))
      (node (ref "U$1") (pin "11") (pinfunction "S1-2_11") (pintype "passive"))
      (node (ref "U$1") (pin "12") (pinfunction "S1-2_12") (pintype "passive"))
      (node (ref "U$1") (pin "13") (pinfunction "S1-2_13") (pintype "passive"))
      (node (ref "U$1") (pin "9") (pinfunction "S1-2_9") (pintype "passive"))
    )
    (net (code "52") (name "Net-(U$10-HO)") (class "Default")
      (node (ref "R55") (pin "1") (pinfunction "1_1") (pintype "passive"))
      (node (ref "U$10") (pin "8") (pinfunction "HO_8") (pintype "output"))
    )
    (net (code "53") (name "Net-(U$10-LO)") (class "Default")
      (node (ref "R56") (pin "1") (pinfunction "1_1") (pintype "passive"))
      (node (ref "U$10") (pin "1") (pinfunction "LO_1") (pintype "output"))
    )
    (net (code "54") (name "Net-(U$10-VCC)") (class "Default")
      (node (ref "C26") (pin "1") (pinfunction "1_1") (pintype "passive"))
      (node (ref "D6") (pin "A") (pinfunction "A_A") (pintype "passive"))
      (node (ref "U$10") (pin "3") (pinfunction "VCC_3") (pintype "power_in"))
    )
    (net (code "55") (name "Net-(U$10-VS)") (class "Default")
      (node (ref "C25") (pin "1") (pinfunction "1_1") (pintype "passive"))
      (node (ref "D7") (pin "C") (pinfunction "C_C") (pintype "passive"))
      (node (ref "D8") (pin "A") (pinfunction "A_A") (pintype "passive"))
      (node (ref "Q3") (pin "S") (pinfunction "S_S") (pintype "passive"))
      (node (ref "Q4") (pin "D") (pinfunction "D_D") (pintype "passive"))
      (node (ref "R58") (pin "2") (pinfunction "2_2") (pintype "passive"))
      (node (ref "R59") (pin "2") (pinfunction "2_2") (pintype "passive"))
      (node (ref "U$1") (pin "1") (pinfunction "P1-1_1") (pintype "passive"))
      (node (ref "U$1") (pin "2") (pinfunction "P1-1_2") (pintype "passive"))
      (node (ref "U$10") (pin "6") (pinfunction "VS_6") (pintype "power_in"))
    )
    (net (code "56") (name "Net-(U1-+VI)") (class "Default")
      (node (ref "C4") (pin "+") (pinfunction "+_+") (pintype "passive"))
      (node (ref "D1") (pin "C") (pinfunction "C_C") (pintype "passive"))
      (node (ref "R1") (pin "1") (pinfunction "1_1") (pintype "passive"))
      (node (ref "U1") (pin "13") (pinfunction "VC_13") (pintype "passive"))
      (node (ref "U1") (pin "15") (pinfunction "+VI_15") (pintype "power_in"))
    )
    (net (code "57") (name "Net-(U1-CT)") (class "Default")
      (node (ref "C7") (pin "2") (pinfunction "2_2") (pintype "passive"))
      (node (ref "R2") (pin "2") (pinfunction "2_2") (pintype "passive"))
      (node (ref "U1") (pin "5") (pinfunction "CT_5") (pintype "passive"))
    )
    (net (code "58") (name "Net-(U1-DISCH)") (class "Default")
      (node (ref "R2") (pin "1") (pinfunction "1_1") (pintype "passive"))
      (node (ref "U1") (pin "7") (pinfunction "DISCH_7") (pintype "passive"))
    )
    (net (code "59") (name "Net-(U1-RT)") (class "Default")
      (node (ref "R6") (pin "1") (pinfunction "1_1") (pintype "passive"))
      (node (ref "U1") (pin "6") (pinfunction "RT_6") (pintype "passive"))
    )
    (net (code "60") (name "Net-(U1-SOFT_START)") (class "Default")
      (node (ref "C6") (pin "+") (pinfunction "+_+") (pintype "passive"))
      (node (ref "U1") (pin "8") (pinfunction "SOFT_START_8") (pintype "passive"))
    )
    (net (code "61") (name "Net-(V+1-P)") (class "Default")
      (node (ref "C30") (pin "+") (pinfunction "+_+") (pintype "passive"))
      (node (ref "OUT-+1") (pin "1") (pinfunction "1_1") (pintype "passive"))
      (node (ref "OUT-+1") (pin "3") (pinfunction "3_3") (pintype "passive"))
      (node (ref "R64") (pin "2") (pinfunction "2_2") (pintype "passive"))
      (node (ref "U$14") (pin "7") (pinfunction "2_7") (pintype "passive"))
      (node (ref "U$14") (pin "8") (pinfunction "2_8") (pintype "passive"))
      (node (ref "U$14") (pin "9") (pinfunction "2_9") (pintype "passive"))
      (node (ref "V+1") (pin "1") (pinfunction "P_1") (pintype "passive"))
    )
    (net (code "62") (name "Net-(X1A-KL)") (class "Default")
      (node (ref "R3") (pin "2") (pinfunction "2_2") (pintype "passive"))
      (node (ref "X1") (pin "1") (pinfunction "KL_1") (pintype "passive"))
    )
    (net (code "63") (name "Net-(X1B-KL)") (class "Default")
      (node (ref "F1") (pin "1") (pinfunction "1_1") (pintype "passive"))
      (node (ref "X1") (pin "2") (pinfunction "KL_2") (pintype "passive"))
    )
    (net (code "64") (name "unconnected-(OUT-+1-Pad4)") (class "Default")
      (node (ref "OUT-+1") (pin "4") (pinfunction "4_4") (pintype "passive"))
    )
    (net (code "65") (name "unconnected-(OUT-1-Pad2)") (class "Default")
      (node (ref "OUT-1") (pin "2") (pinfunction "2_2") (pintype "passive"))
    )
    (net (code "66") (name "unconnected-(R61-Pad2)") (class "Default")
      (node (ref "R61") (pin "2") (pinfunction "2_2") (pintype "passive"))
    )
    (net (code "67") (name "unconnected-(U$10-SD-Pad13)") (class "Default")
      (node (ref "U$10") (pin "13") (pinfunction "SD_13") (pintype "input"))
    )
    (net (code "68") (name "unconnected-(U$11-K-PadP$1)") (class "Default")
      (node (ref "U$11") (pin "P$1") (pinfunction "K_P$1") (pintype "passive"))
    )
    (net (code "69") (name "unconnected-(U$12-K-PadP$1)") (class "Default")
      (node (ref "U$12") (pin "P$1") (pinfunction "K_P$1") (pintype "passive"))
    )
    (net (code "70") (name "unconnected-(U$15-K-PadP$1)") (class "Default")
      (node (ref "U$15") (pin "P$1") (pinfunction "K_P$1") (pintype "passive"))
    )
    (net (code "71") (name "unconnected-(U$16-K-PadP$1)") (class "Default")
      (node (ref "U$16") (pin "P$1") (pinfunction "K_P$1") (pintype "passive"))
    )
    (net (code "72") (name "unconnected-(U1-COMP-Pad9)") (class "Default")
      (node (ref "U1") (pin "9") (pinfunction "COMP_9") (pintype "passive"))
    )
    (net (code "73") (name "unconnected-(U1-INV.IN-Pad1)") (class "Default")
      (node (ref "U1") (pin "1") (pinfunction "INV.IN_1") (pintype "input"))
    )
    (net (code "74") (name "unconnected-(U1-N.I.IN-Pad2)") (class "Default")
      (node (ref "U1") (pin "2") (pinfunction "N.I.IN_2") (pintype "input"))
    )
    (net (code "75") (name "unconnected-(U1-OSC.OUT-Pad4)") (class "Default")
      (node (ref "U1") (pin "4") (pinfunction "OSC.OUT_4") (pintype "output"))
    )
    (net (code "76") (name "unconnected-(U1-SYNC-Pad3)") (class "Default")
      (node (ref "U1") (pin "3") (pinfunction "SYNC_3") (pintype "passive"))
    )
    (net (code "77") (name "unconnected-(U1-VREF-Pad16)") (class "Default")
      (node (ref "U1") (pin "16") (pinfunction "VREF_16") (pintype "passive"))
    )
  )
)
